# bloenk_final.net
KiCad netlist of a schematic drawn in EAGLE
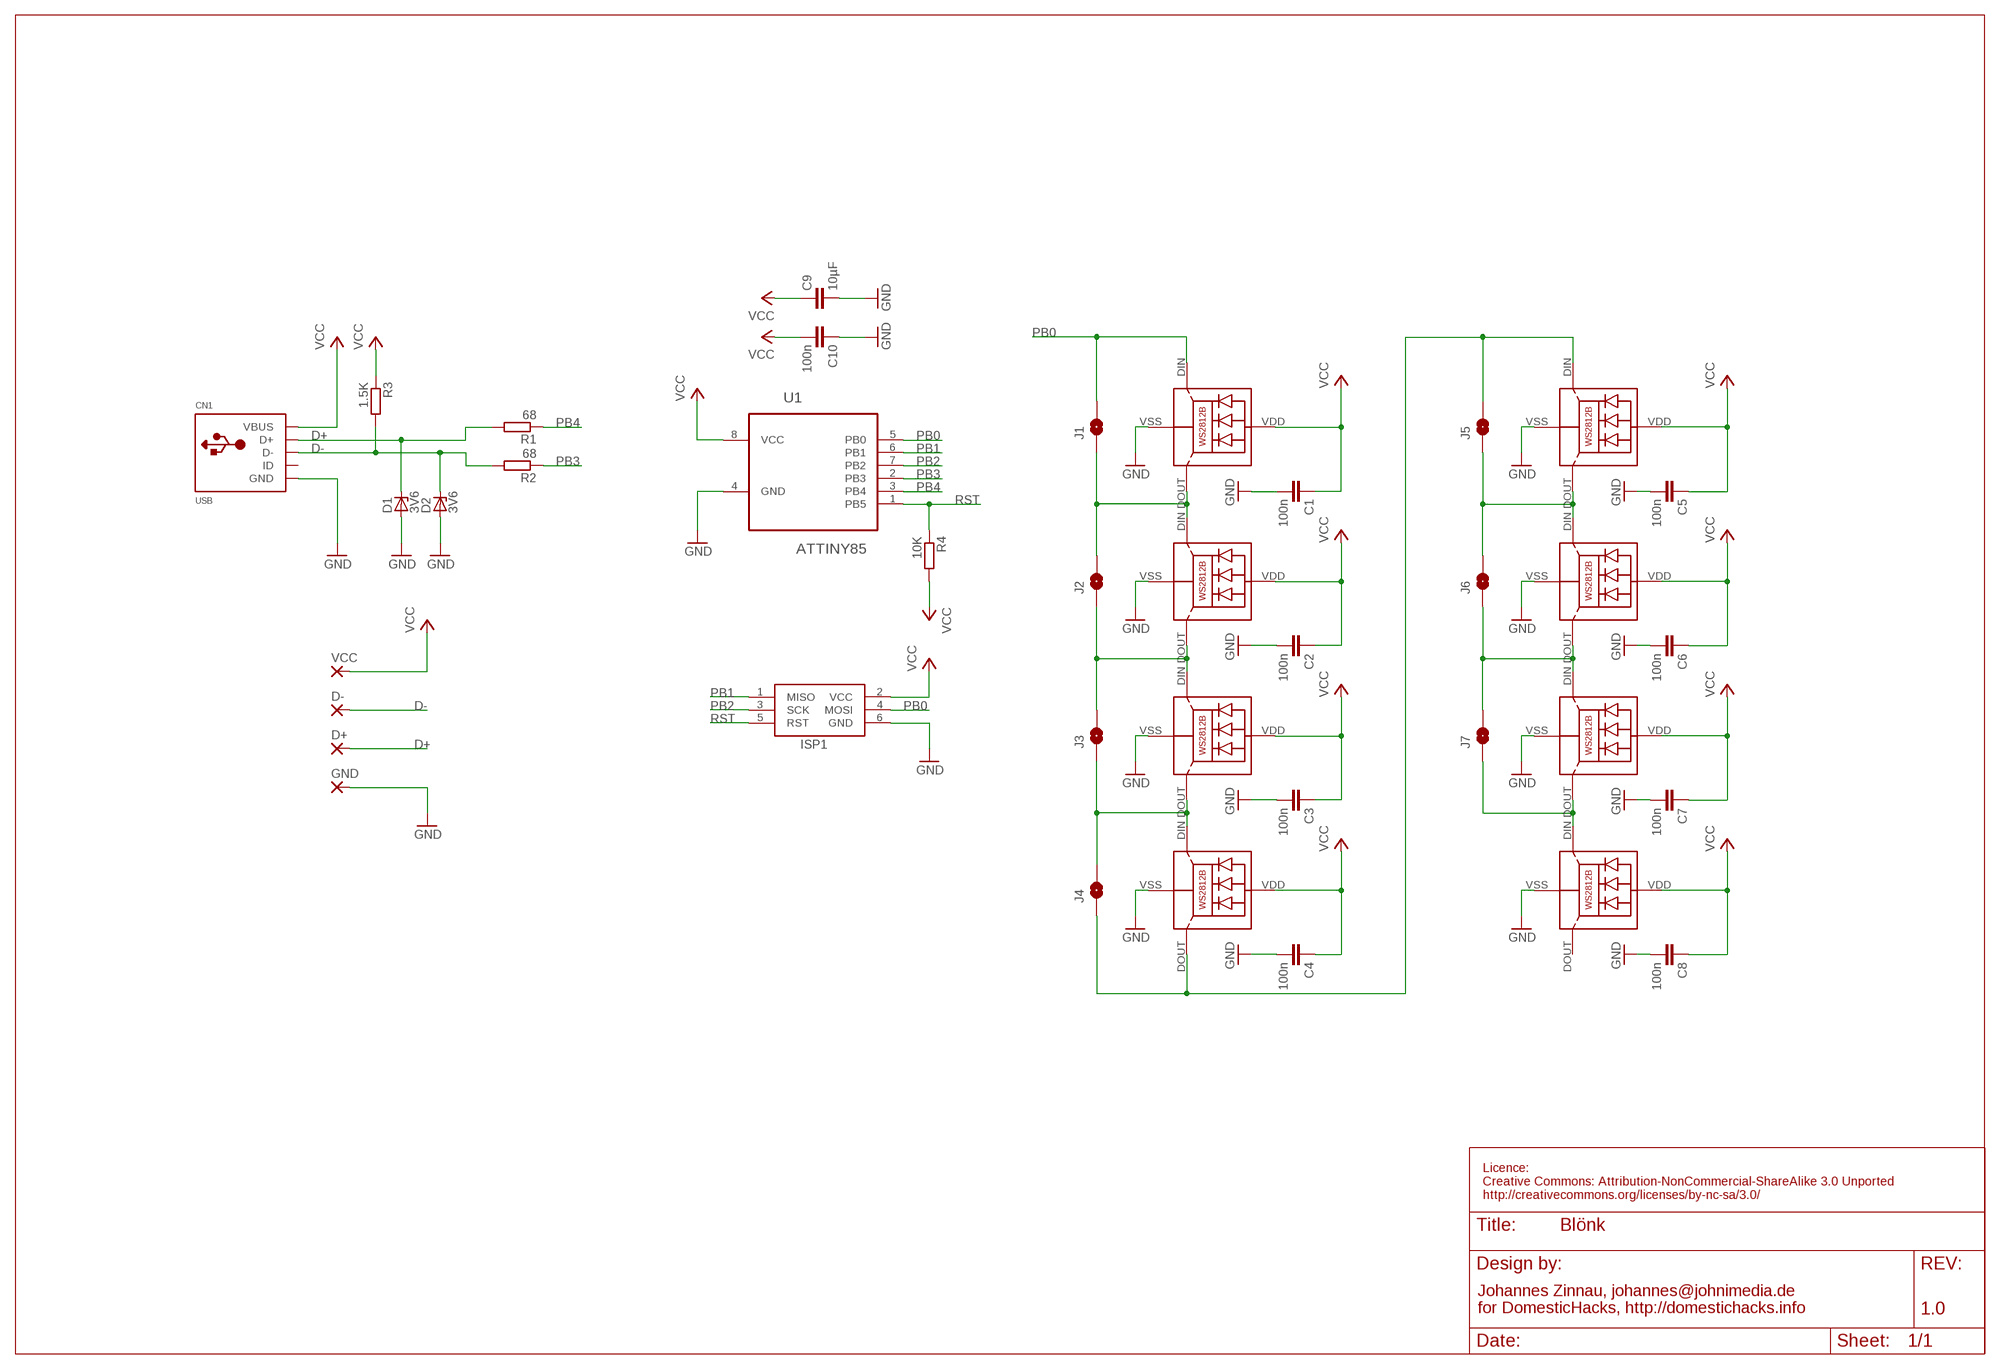
[diagram p0: schematic, sheet 1]

(export (version "E")
  (design (tool "Eeschema 10.0.6"))
  (components
    (comp (ref "C1")
      (value "100n")
      (footprint "eagle-import:C0603")
      (libsource (lib "eagle-import") (part "resistor_C-EUC0603"))
    )
    (comp (ref "C2")
      (value "100n")
      (footprint "eagle-import:C0603")
      (libsource (lib "eagle-import") (part "resistor_C-EUC0603"))
    )
    (comp (ref "C3")
      (value "100n")
      (footprint "eagle-import:C0603")
      (libsource (lib "eagle-import") (part "resistor_C-EUC0603"))
    )
    (comp (ref "C4")
      (value "100n")
      (footprint "eagle-import:C0603")
      (libsource (lib "eagle-import") (part "resistor_C-EUC0603"))
    )
    (comp (ref "C5")
      (value "100n")
      (footprint "eagle-import:C0603")
      (libsource (lib "eagle-import") (part "resistor_C-EUC0603"))
    )
    (comp (ref "C6")
      (value "100n")
      (footprint "eagle-import:C0603")
      (libsource (lib "eagle-import") (part "resistor_C-EUC0603"))
    )
    (comp (ref "C7")
      (value "100n")
      (footprint "eagle-import:C0603")
      (libsource (lib "eagle-import") (part "resistor_C-EUC0603"))
    )
    (comp (ref "C8")
      (value "100n")
      (footprint "eagle-import:C0603")
      (libsource (lib "eagle-import") (part "resistor_C-EUC0603"))
    )
    (comp (ref "C9")
      (value "10µF")
      (footprint "eagle-import:C0805")
      (libsource (lib "eagle-import") (part "C-EUC0805"))
    )
    (comp (ref "C10")
      (value "100n")
      (footprint "eagle-import:C0603")
      (libsource (lib "eagle-import") (part "resistor_C-EUC0603"))
    )
    (comp (ref "CN1")
      (value "USB")
      (footprint "eagle-import:USB-MINIB")
      (libsource (lib "eagle-import") (part "USBMINIB"))
    )
    (comp (ref "D+")
      (value "SMD2")
      (footprint "eagle-import:SMD1,27-2,54")
      (libsource (lib "eagle-import") (part "SMD2"))
    )
    (comp (ref "D-")
      (value "SMD2")
      (footprint "eagle-import:SMD1,27-2,54")
      (libsource (lib "eagle-import") (part "SMD2"))
    )
    (comp (ref "D1")
      (value "3V6")
      (footprint "eagle-import:SOD80C")
      (libsource (lib "eagle-import") (part "ZENER-DIODESOD80C"))
    )
    (comp (ref "D2")
      (value "3V6")
      (footprint "eagle-import:SOD80C")
      (libsource (lib "eagle-import") (part "ZENER-DIODESOD80C"))
    )
    (comp (ref "GND")
      (value "SMD2")
      (footprint "eagle-import:SMD1,27-2,54")
      (libsource (lib "eagle-import") (part "SMD2"))
    )
    (comp (ref "ISP1")
      (value "AVRISP-6")
      (footprint "eagle-import:AVRISP")
      (libsource (lib "eagle-import") (part "AVRISP-6"))
    )
    (comp (ref "J1")
      (value "SOLDERJUMPERNO")
      (footprint "eagle-import:SJ_2S-NO")
      (libsource (lib "eagle-import") (part "SOLDERJUMPERNO"))
    )
    (comp (ref "J2")
      (value "SOLDERJUMPERNO")
      (footprint "eagle-import:SJ_2S-NO")
      (libsource (lib "eagle-import") (part "SOLDERJUMPERNO"))
    )
    (comp (ref "J3")
      (value "SOLDERJUMPERNO")
      (footprint "eagle-import:SJ_2S-NO")
      (libsource (lib "eagle-import") (part "SOLDERJUMPERNO"))
    )
    (comp (ref "J4")
      (value "SOLDERJUMPERNO")
      (footprint "eagle-import:SJ_2S-NO")
      (libsource (lib "eagle-import") (part "SOLDERJUMPERNO"))
    )
    (comp (ref "J5")
      (value "SOLDERJUMPERNO")
      (footprint "eagle-import:SJ_2S-NO")
      (libsource (lib "eagle-import") (part "SOLDERJUMPERNO"))
    )
    (comp (ref "J6")
      (value "SOLDERJUMPERNO")
      (footprint "eagle-import:SJ_2S-NO")
      (libsource (lib "eagle-import") (part "SOLDERJUMPERNO"))
    )
    (comp (ref "J7")
      (value "SOLDERJUMPERNO")
      (footprint "eagle-import:SJ_2S-NO")
      (libsource (lib "eagle-import") (part "SOLDERJUMPERNO"))
    )
    (comp (ref "LED1")
      (value "WS2812B")
      (footprint "eagle-import:WS2812B")
      (libsource (lib "eagle-import") (part "WS2812B"))
    )
    (comp (ref "LED2")
      (value "WS2812B")
      (footprint "eagle-import:WS2812B")
      (libsource (lib "eagle-import") (part "WS2812B"))
    )
    (comp (ref "LED3")
      (value "WS2812B")
      (footprint "eagle-import:WS2812B")
      (libsource (lib "eagle-import") (part "WS2812B"))
    )
    (comp (ref "LED4")
      (value "WS2812B")
      (footprint "eagle-import:WS2812B")
      (libsource (lib "eagle-import") (part "WS2812B"))
    )
    (comp (ref "LED5")
      (value "WS2812B")
      (footprint "eagle-import:WS2812B")
      (libsource (lib "eagle-import") (part "WS2812B"))
    )
    (comp (ref "LED6")
      (value "WS2812B")
      (footprint "eagle-import:WS2812B")
      (libsource (lib "eagle-import") (part "WS2812B"))
    )
    (comp (ref "LED7")
      (value "WS2812B")
      (footprint "eagle-import:WS2812B")
      (libsource (lib "eagle-import") (part "WS2812B"))
    )
    (comp (ref "LED8")
      (value "WS2812B")
      (footprint "eagle-import:WS2812B")
      (libsource (lib "eagle-import") (part "WS2812B"))
    )
    (comp (ref "R1")
      (value "68")
      (footprint "eagle-import:R0603")
      (libsource (lib "eagle-import") (part "R-EU_R0603"))
    )
    (comp (ref "R2")
      (value "68")
      (footprint "eagle-import:R0603")
      (libsource (lib "eagle-import") (part "R-EU_R0603"))
    )
    (comp (ref "R3")
      (value "1.5K")
      (footprint "eagle-import:R0603")
      (libsource (lib "eagle-import") (part "R-EU_R0603"))
    )
    (comp (ref "R4")
      (value "10K")
      (footprint "eagle-import:R0603")
      (libsource (lib "eagle-import") (part "R-EU_R0603"))
    )
    (comp (ref "U1")
      (value "ATTINY85")
      (footprint "eagle-import:SOIC127P798X216-8N")
      (fields (field (name "MPN") "ATTINY85-20SU"))
      (libsource (lib "eagle-import") (part "ATTINY85-20SU"))
    )
    (comp (ref "VCC")
      (value "SMD2")
      (footprint "eagle-import:SMD1,27-2,54")
      (libsource (lib "eagle-import") (part "SMD2"))
    )
  )
  (nets
    (net (code "1") (name "/D+") (class "Default")
      (node (ref "CN1") (pin "D+") (pinfunction "D+_D+") (pintype "bidirectional"))
      (node (ref "D+") (pin "1") (pinfunction "P_1") (pintype "passive"))
      (node (ref "D1") (pin "C") (pinfunction "C_C") (pintype "passive"))
      (node (ref "R1") (pin "2") (pinfunction "2_2") (pintype "passive"))
    )
    (net (code "2") (name "/D-") (class "Default")
      (node (ref "CN1") (pin "D-") (pinfunction "D-_D-") (pintype "bidirectional"))
      (node (ref "D-") (pin "1") (pinfunction "P_1") (pintype "passive"))
      (node (ref "D2") (pin "C") (pinfunction "C_C") (pintype "passive"))
      (node (ref "R2") (pin "2") (pinfunction "2_2") (pintype "passive"))
      (node (ref "R3") (pin "2") (pinfunction "2_2") (pintype "passive"))
    )
    (net (code "3") (name "/PB0") (class "Default")
      (node (ref "ISP1") (pin "4") (pinfunction "MOSI_4") (pintype "output"))
      (node (ref "J1") (pin "2") (pinfunction "2_2") (pintype "passive"))
      (node (ref "LED1") (pin "DIN") (pinfunction "DI_DIN") (pintype "input"))
      (node (ref "U1") (pin "5") (pinfunction "PB0_5") (pintype "bidirectional"))
    )
    (net (code "4") (name "/PB1") (class "Default")
      (node (ref "ISP1") (pin "1") (pinfunction "MISO_1") (pintype "input"))
      (node (ref "U1") (pin "6") (pinfunction "PB1_6") (pintype "bidirectional"))
    )
    (net (code "5") (name "/PB2") (class "Default")
      (node (ref "ISP1") (pin "3") (pinfunction "SCK_3") (pintype "output"))
      (node (ref "U1") (pin "7") (pinfunction "PB2_7") (pintype "bidirectional"))
    )
    (net (code "6") (name "/PB3") (class "Default")
      (node (ref "R2") (pin "1") (pinfunction "1_1") (pintype "passive"))
      (node (ref "U1") (pin "2") (pinfunction "PB3_2") (pintype "bidirectional"))
    )
    (net (code "7") (name "/PB4") (class "Default")
      (node (ref "R1") (pin "1") (pinfunction "1_1") (pintype "passive"))
      (node (ref "U1") (pin "3") (pinfunction "PB4_3") (pintype "bidirectional"))
    )
    (net (code "8") (name "/RST") (class "Default")
      (node (ref "ISP1") (pin "5") (pinfunction "RST_5") (pintype "output"))
      (node (ref "R4") (pin "1") (pinfunction "1_1") (pintype "passive"))
      (node (ref "U1") (pin "1") (pinfunction "PB5_1") (pintype "bidirectional"))
    )
    (net (code "9") (name "GND") (class "Default")
      (node (ref "C1") (pin "2") (pinfunction "2_2") (pintype "passive"))
      (node (ref "C10") (pin "1") (pinfunction "1_1") (pintype "passive"))
      (node (ref "C2") (pin "2") (pinfunction "2_2") (pintype "passive"))
      (node (ref "C3") (pin "2") (pinfunction "2_2") (pintype "passive"))
      (node (ref "C4") (pin "2") (pinfunction "2_2") (pintype "passive"))
      (node (ref "C5") (pin "2") (pinfunction "2_2") (pintype "passive"))
      (node (ref "C6") (pin "2") (pinfunction "2_2") (pintype "passive"))
      (node (ref "C7") (pin "2") (pinfunction "2_2") (pintype "passive"))
      (node (ref "C8") (pin "2") (pinfunction "2_2") (pintype "passive"))
      (node (ref "C9") (pin "2") (pinfunction "2_2") (pintype "passive"))
      (node (ref "CN1") (pin "GND") (pinfunction "GND_GND") (pintype "power_in"))
      (node (ref "D1") (pin "A") (pinfunction "A_A") (pintype "passive"))
      (node (ref "D2") (pin "A") (pinfunction "A_A") (pintype "passive"))
      (node (ref "GND") (pin "1") (pinfunction "P_1") (pintype "passive"))
      (node (ref "ISP1") (pin "6") (pinfunction "GND_6") (pintype "power_in"))
      (node (ref "LED1") (pin "VSS") (pinfunction "GND_VSS") (pintype "power_in"))
      (node (ref "LED2") (pin "VSS") (pinfunction "GND_VSS") (pintype "power_in"))
      (node (ref "LED3") (pin "VSS") (pinfunction "GND_VSS") (pintype "power_in"))
      (node (ref "LED4") (pin "VSS") (pinfunction "GND_VSS") (pintype "power_in"))
      (node (ref "LED5") (pin "VSS") (pinfunction "GND_VSS") (pintype "power_in"))
      (node (ref "LED6") (pin "VSS") (pinfunction "GND_VSS") (pintype "power_in"))
      (node (ref "LED7") (pin "VSS") (pinfunction "GND_VSS") (pintype "power_in"))
      (node (ref "LED8") (pin "VSS") (pinfunction "GND_VSS") (pintype "power_in"))
      (node (ref "U1") (pin "4") (pinfunction "GND_4") (pintype "passive"))
    )
    (net (code "10") (name "Net-(LED1-DO)") (class "Default")
      (node (ref "J1") (pin "1") (pinfunction "1_1") (pintype "passive"))
      (node (ref "J2") (pin "2") (pinfunction "2_2") (pintype "passive"))
      (node (ref "LED1") (pin "DOUT") (pinfunction "DO_DOUT") (pintype "output"))
      (node (ref "LED2") (pin "DIN") (pinfunction "DI_DIN") (pintype "input"))
    )
    (net (code "11") (name "Net-(LED2-DO)") (class "Default")
      (node (ref "J2") (pin "1") (pinfunction "1_1") (pintype "passive"))
      (node (ref "J3") (pin "2") (pinfunction "2_2") (pintype "passive"))
      (node (ref "LED2") (pin "DOUT") (pinfunction "DO_DOUT") (pintype "output"))
      (node (ref "LED3") (pin "DIN") (pinfunction "DI_DIN") (pintype "input"))
    )
    (net (code "12") (name "Net-(LED3-DO)") (class "Default")
      (node (ref "J3") (pin "1") (pinfunction "1_1") (pintype "passive"))
      (node (ref "J4") (pin "2") (pinfunction "2_2") (pintype "passive"))
      (node (ref "LED3") (pin "DOUT") (pinfunction "DO_DOUT") (pintype "output"))
      (node (ref "LED4") (pin "DIN") (pinfunction "DI_DIN") (pintype "input"))
    )
    (net (code "13") (name "Net-(LED4-DO)") (class "Default")
      (node (ref "J4") (pin "1") (pinfunction "1_1") (pintype "passive"))
      (node (ref "J5") (pin "2") (pinfunction "2_2") (pintype "passive"))
      (node (ref "LED4") (pin "DOUT") (pinfunction "DO_DOUT") (pintype "output"))
      (node (ref "LED5") (pin "DIN") (pinfunction "DI_DIN") (pintype "input"))
    )
    (net (code "14") (name "Net-(LED5-DO)") (class "Default")
      (node (ref "J5") (pin "1") (pinfunction "1_1") (pintype "passive"))
      (node (ref "J6") (pin "2") (pinfunction "2_2") (pintype "passive"))
      (node (ref "LED5") (pin "DOUT") (pinfunction "DO_DOUT") (pintype "output"))
      (node (ref "LED6") (pin "DIN") (pinfunction "DI_DIN") (pintype "input"))
    )
    (net (code "15") (name "Net-(LED6-DO)") (class "Default")
      (node (ref "J6") (pin "1") (pinfunction "1_1") (pintype "passive"))
      (node (ref "J7") (pin "2") (pinfunction "2_2") (pintype "passive"))
      (node (ref "LED6") (pin "DOUT") (pinfunction "DO_DOUT") (pintype "output"))
      (node (ref "LED7") (pin "DIN") (pinfunction "DI_DIN") (pintype "input"))
    )
    (net (code "16") (name "Net-(LED7-DO)") (class "Default")
      (node (ref "J7") (pin "1") (pinfunction "1_1") (pintype "passive"))
      (node (ref "LED7") (pin "DOUT") (pinfunction "DO_DOUT") (pintype "output"))
      (node (ref "LED8") (pin "DIN") (pinfunction "DI_DIN") (pintype "input"))
    )
    (net (code "17") (name "VCC") (class "Default")
      (node (ref "C1") (pin "1") (pinfunction "1_1") (pintype "passive"))
      (node (ref "C10") (pin "2") (pinfunction "2_2") (pintype "passive"))
      (node (ref "C2") (pin "1") (pinfunction "1_1") (pintype "passive"))
      (node (ref "C3") (pin "1") (pinfunction "1_1") (pintype "passive"))
      (node (ref "C4") (pin "1") (pinfunction "1_1") (pintype "passive"))
      (node (ref "C5") (pin "1") (pinfunction "1_1") (pintype "passive"))
      (node (ref "C6") (pin "1") (pinfunction "1_1") (pintype "passive"))
      (node (ref "C7") (pin "1") (pinfunction "1_1") (pintype "passive"))
      (node (ref "C8") (pin "1") (pinfunction "1_1") (pintype "passive"))
      (node (ref "C9") (pin "1") (pinfunction "1_1") (pintype "passive"))
      (node (ref "CN1") (pin "VBUS") (pinfunction "VBUS_VBUS") (pintype "power_in"))
      (node (ref "ISP1") (pin "2") (pinfunction "VCC_2") (pintype "power_in"))
      (node (ref "LED1") (pin "VDD") (pinfunction "VDD_VDD") (pintype "power_in"))
      (node (ref "LED2") (pin "VDD") (pinfunction "VDD_VDD") (pintype "power_in"))
      (node (ref "LED3") (pin "VDD") (pinfunction "VDD_VDD") (pintype "power_in"))
      (node (ref "LED4") (pin "VDD") (pinfunction "VDD_VDD") (pintype "power_in"))
      (node (ref "LED5") (pin "VDD") (pinfunction "VDD_VDD") (pintype "power_in"))
      (node (ref "LED6") (pin "VDD") (pinfunction "VDD_VDD") (pintype "power_in"))
      (node (ref "LED7") (pin "VDD") (pinfunction "VDD_VDD") (pintype "power_in"))
      (node (ref "LED8") (pin "VDD") (pinfunction "VDD_VDD") (pintype "power_in"))
      (node (ref "R3") (pin "1") (pinfunction "1_1") (pintype "passive"))
      (node (ref "R4") (pin "2") (pinfunction "2_2") (pintype "passive"))
      (node (ref "U1") (pin "8") (pinfunction "VCC_8") (pintype "power_in"))
      (node (ref "VCC") (pin "1") (pinfunction "P_1") (pintype "passive"))
    )
    (net (code "18") (name "unconnected-(CN1-PadID)") (class "Default")
      (node (ref "CN1") (pin "ID") (pinfunction "ID_ID") (pintype "bidirectional"))
    )
    (net (code "19") (name "unconnected-(LED8-DO-PadDOUT)") (class "Default")
      (node (ref "LED8") (pin "DOUT") (pinfunction "DO_DOUT") (pintype "output"))
    )
  )
)
